# MCU.net
KiCad netlist of a schematic drawn in Altium Designer
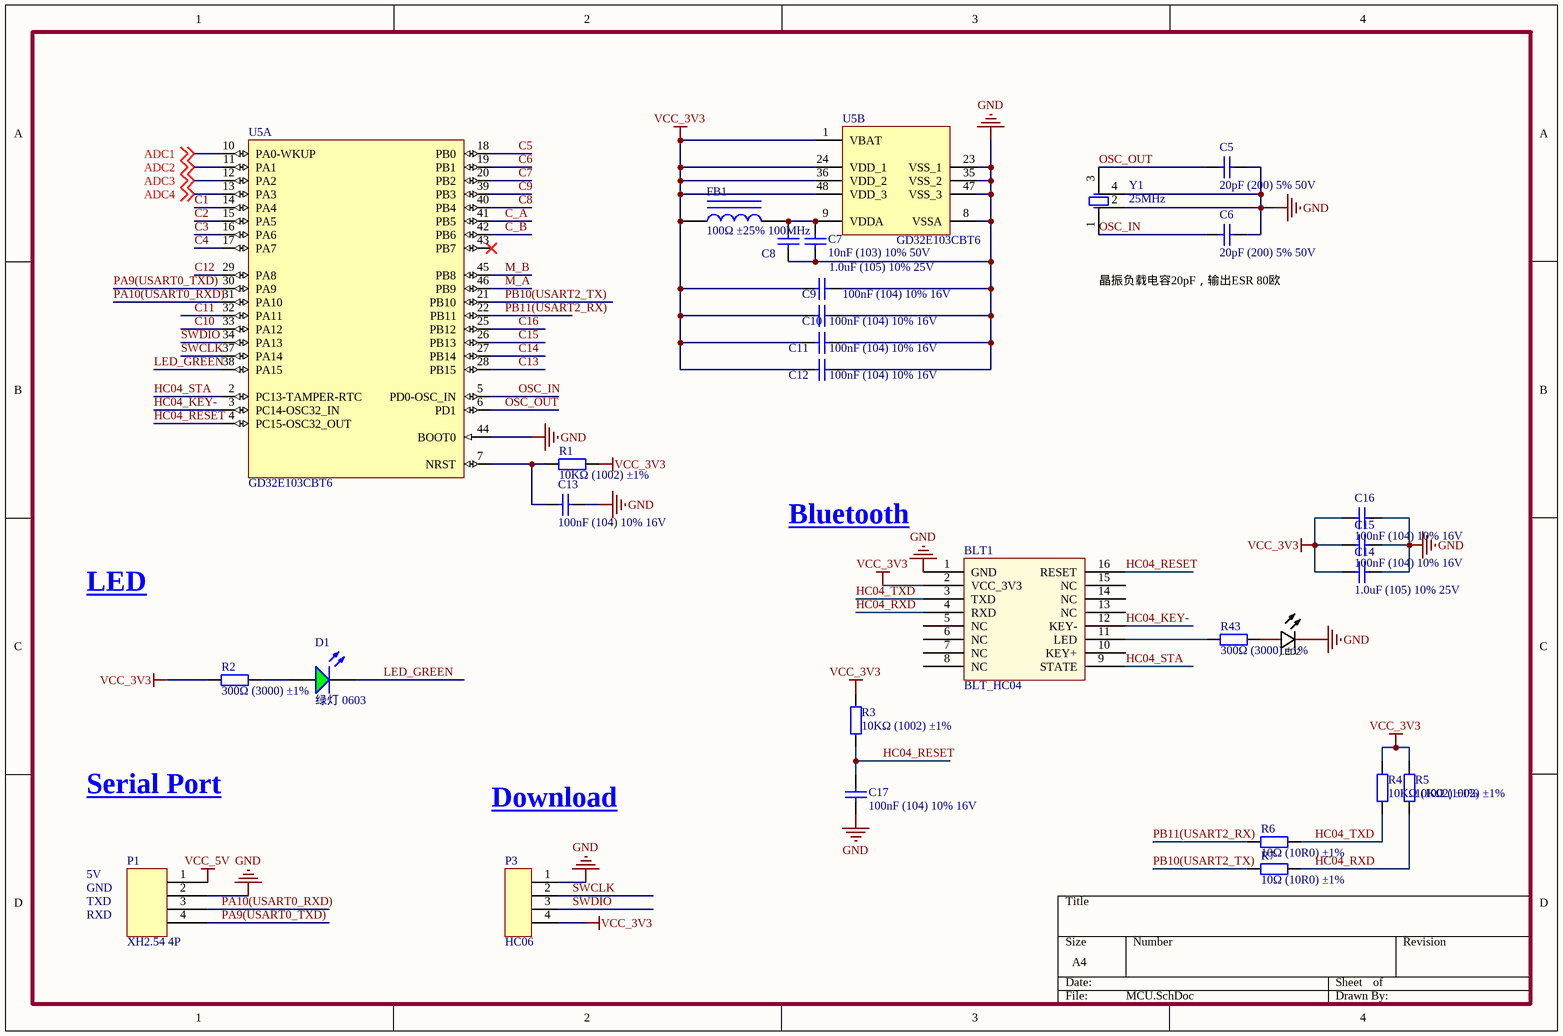
[diagram p0: MCU.SchDoc]

(export (version "E")
  (design (tool "Eeschema 10.0.6"))
  (components
    (comp (ref "BLT1")
      (value "BLT_HC04")
      (footprint "HC04_BLT")
      (libsource (lib "32x64_GD32E103VBT6") (part "BLT_HC04"))
    )
    (comp (ref "C5")
      (value "20pF (200) 5% 50V")
      (footprint "0402_C")
      (description "贴片电容")
      (libsource (lib "Miscellaneous Devices LC") (part "0402 20pF (200) 5% 50V"))
    )
    (comp (ref "C6")
      (value "20pF (200) 5% 50V")
      (footprint "0402_C")
      (description "贴片电容")
      (libsource (lib "Miscellaneous Devices LC") (part "0402 20pF (200) 5% 50V"))
    )
    (comp (ref "C7")
      (value "10nF (103) 10% 50V")
      (footprint "0402_C")
      (description "贴片电容")
      (libsource (lib "Miscellaneous Devices LC") (part "0402 10nF (103) 10% 50V"))
    )
    (comp (ref "C8")
      (value "1.0uF (105) 10% 25V")
      (footprint "0402_C")
      (description "贴片电容")
      (libsource (lib "EMOWHH Make") (part "0402-C"))
    )
    (comp (ref "C9")
      (value "100nF (104) 10% 16V")
      (footprint "0402_C")
      (description "贴片电容")
      (libsource (lib "EMOWHH Make") (part "0402-C"))
    )
    (comp (ref "C10")
      (value "100nF (104) 10% 16V")
      (footprint "0402_C")
      (description "贴片电容")
      (libsource (lib "EMOWHH Make") (part "0402-C"))
    )
    (comp (ref "C11")
      (value "100nF (104) 10% 16V")
      (footprint "0402_C")
      (description "贴片电容")
      (libsource (lib "EMOWHH Make") (part "0402-C"))
    )
    (comp (ref "C12")
      (value "100nF (104) 10% 16V")
      (footprint "0402_C")
      (description "贴片电容")
      (libsource (lib "EMOWHH Make") (part "0402-C"))
    )
    (comp (ref "C13")
      (value "100nF (104) 10% 16V")
      (footprint "0402_C")
      (description "贴片电容")
      (libsource (lib "Miscellaneous Devices LC") (part "0402 100nF (104) 10% 16V"))
    )
    (comp (ref "C14")
      (value "1.0uF (105) 10% 25V")
      (footprint "0402_C")
      (description "贴片电容")
      (libsource (lib "32x64_GD32E103VBT6") (part "0402 1.0uF (105) 10% 25V"))
    )
    (comp (ref "C15")
      (value "100nF (104) 10% 16V")
      (footprint "0402_C")
      (description "贴片电容")
      (libsource (lib "32x64_GD32E103VBT6") (part "0402 100nF (104) 10% 16V"))
    )
    (comp (ref "C16")
      (value "100nF (104) 10% 16V")
      (footprint "0402_C")
      (description "贴片电容")
      (libsource (lib "32x64_GD32E103VBT6") (part "0402 100nF (104) 10% 16V"))
    )
    (comp (ref "C17")
      (value "100nF (104) 10% 16V")
      (footprint "0402_C")
      (description "贴片电容")
      (libsource (lib "32x64_GD32E103VBT6") (part "0402 100nF (104) 10% 16V"))
    )
    (comp (ref "D1")
      (value "绿灯 0603")
      (footprint "0603_LED_S1")
      (description "发光二极管")
      (libsource (lib "Miscellaneous Devices LC") (part "0603 绿灯"))
    )
    (comp (ref "FB1")
      (value "100Ω ±25% 100MHz")
      (footprint "0805_L")
      (description "贴片磁珠")
      (libsource (lib "Miscellaneous Devices LC") (part "0805 100Ω 25% 100MHz"))
    )
    (comp (ref "LED2")
      (value "0603")
      (footprint "LED0603-RD")
      (description "0603 LED 蓝")
      (fields (field (name "MANUFACTURER") "国星光电") (field (name "MANUFACTURER PART") "NCD0603B4"))
      (libsource (lib "医疗床PCB") (part "0603 LED 蓝"))
    )
    (comp (ref "P1")
      (value "XH2.54 4P")
      (footprint "HC06")
      (libsource (lib "chaoning_Integrated_Library") (part "XH2.54 4P"))
    )
    (comp (ref "P3") (value "HC06") (footprint "HC06") (libsource (lib "EMOWHH Make") (part "HC06")))
    (comp (ref "R1")
      (value "10KΩ (1002) ±1%")
      (footprint "0402_R")
      (description "贴片电阻")
      (libsource (lib "Miscellaneous Devices LC") (part "0402 10KΩ (1002) 1%"))
    )
    (comp (ref "R2")
      (value "300Ω (3000) ±1%")
      (footprint "0402_R")
      (description "贴片电阻")
      (libsource (lib "") (part "0402 300Ω (3000) 1%_1"))
    )
    (comp (ref "R3")
      (value "10KΩ (1002) ±1%")
      (footprint "0402_R")
      (description "贴片电阻")
      (libsource (lib "32x64_GD32E103VBT6") (part "0402 10KΩ (1002) 1%"))
    )
    (comp (ref "R4")
      (value "10KΩ (1002) ±1%")
      (footprint "0402_R")
      (description "贴片电阻")
      (libsource (lib "32x64_GD32E103VBT6") (part "0402 10KΩ (1002) 1%"))
    )
    (comp (ref "R5")
      (value "10KΩ (1002) ±1%")
      (footprint "0402_R")
      (description "贴片电阻")
      (libsource (lib "32x64_GD32E103VBT6") (part "0402 10KΩ (1002) 1%"))
    )
    (comp (ref "R6")
      (value "10Ω (10R0) ±1%")
      (footprint "0402_R")
      (description "贴片电阻")
      (libsource (lib "32x64_GD32E103VBT6") (part "0402 10Ω (10R0) 1%"))
    )
    (comp (ref "R7")
      (value "10Ω (10R0) ±1%")
      (footprint "0402_R")
      (description "贴片电阻")
      (libsource (lib "32x64_GD32E103VBT6") (part "0402 10Ω (10R0) 1%"))
    )
    (comp (ref "R43")
      (value "300Ω (3000) ±1%")
      (footprint "0402_R")
      (description "贴片电阻")
      (libsource (lib "Miscellaneous Devices LC") (part "0402 300Ω (3000) 1%"))
    )
    (comp (ref "U5")
      (value "GD32E103CBT6")
      (footprint "LQFP48_N")
      (libsource (lib "dm-sch_library") (part "GD32E103CBT6"))
    )
    (comp (ref "Y1")
      (value "25MHz")
      (footprint "3225")
      (description "Crystal Oscillator")
      (fields (field (name "PUBLISHER") "Altium Limited"))
      (libsource (lib "chaoning_Integrated_Library") (part "XTAL-4"))
    )
  )
  (nets
    (net (code "2") (name "/C1") (class "Default")
      (node (ref "U5") (pin "14") (pinfunction "PA4_14") (pintype "bidirectional"))
    )
    (net (code "3") (name "/C2") (class "Default")
      (node (ref "U5") (pin "15") (pinfunction "PA5_15") (pintype "bidirectional"))
    )
    (net (code "4") (name "/C3") (class "Default")
      (node (ref "U5") (pin "16") (pinfunction "PA6_16") (pintype "bidirectional"))
    )
    (net (code "5") (name "/C4") (class "Default")
      (node (ref "U5") (pin "17") (pinfunction "PA7_17") (pintype "bidirectional"))
    )
    (net (code "6") (name "/C5") (class "Default")
      (node (ref "U5") (pin "18") (pinfunction "PB0_18") (pintype "bidirectional"))
    )
    (net (code "7") (name "/C6") (class "Default")
      (node (ref "U5") (pin "19") (pinfunction "PB1_19") (pintype "bidirectional"))
    )
    (net (code "8") (name "/C7") (class "Default")
      (node (ref "U5") (pin "20") (pinfunction "PB2_20") (pintype "bidirectional"))
    )
    (net (code "9") (name "/C8") (class "Default")
      (node (ref "U5") (pin "40") (pinfunction "PB4_40") (pintype "bidirectional"))
    )
    (net (code "10") (name "/C9") (class "Default")
      (node (ref "U5") (pin "39") (pinfunction "PB3_39") (pintype "bidirectional"))
    )
    (net (code "11") (name "/C10") (class "Default")
      (node (ref "U5") (pin "33") (pinfunction "PA12_33") (pintype "bidirectional"))
    )
    (net (code "12") (name "/C11") (class "Default")
      (node (ref "U5") (pin "32") (pinfunction "PA11_32") (pintype "bidirectional"))
    )
    (net (code "13") (name "/C12") (class "Default")
      (node (ref "U5") (pin "29") (pinfunction "PA8_29") (pintype "bidirectional"))
    )
    (net (code "14") (name "/C13") (class "Default")
      (node (ref "U5") (pin "28") (pinfunction "PB15_28") (pintype "bidirectional"))
    )
    (net (code "15") (name "/C14") (class "Default")
      (node (ref "U5") (pin "27") (pinfunction "PB14_27") (pintype "bidirectional"))
    )
    (net (code "16") (name "/C15") (class "Default")
      (node (ref "U5") (pin "26") (pinfunction "PB13_26") (pintype "bidirectional"))
    )
    (net (code "17") (name "/C16") (class "Default")
      (node (ref "U5") (pin "25") (pinfunction "PB12_25") (pintype "bidirectional"))
    )
    (net (code "18") (name "/C_A") (class "Default")
      (node (ref "U5") (pin "41") (pinfunction "PB5_41") (pintype "bidirectional"))
    )
    (net (code "19") (name "/C_B") (class "Default")
      (node (ref "U5") (pin "42") (pinfunction "PB6_42") (pintype "bidirectional"))
    )
    (net (code "20") (name "/HC04_KEY-") (class "Default")
      (node (ref "BLT1") (pin "12") (pinfunction "KEY-_12") (pintype "passive"))
      (node (ref "U5") (pin "3") (pinfunction "PC14-OSC32_IN_3") (pintype "bidirectional"))
    )
    (net (code "21") (name "/HC04_RESET") (class "Default")
      (node (ref "BLT1") (pin "16") (pinfunction "RESET_16") (pintype "passive"))
      (node (ref "C17") (pin "2") (pinfunction "2_2") (pintype "passive"))
      (node (ref "R3") (pin "1") (pinfunction "1_1") (pintype "passive"))
      (node (ref "U5") (pin "4") (pinfunction "PC15-OSC32_OUT_4") (pintype "bidirectional"))
    )
    (net (code "22") (name "/HC04_RXD") (class "Default")
      (node (ref "BLT1") (pin "4") (pinfunction "RXD_4") (pintype "passive"))
      (node (ref "R5") (pin "1") (pinfunction "1_1") (pintype "passive"))
      (node (ref "R7") (pin "2") (pinfunction "2_2") (pintype "passive"))
    )
    (net (code "23") (name "/HC04_STA") (class "Default")
      (node (ref "BLT1") (pin "9") (pinfunction "STATE_9") (pintype "passive"))
      (node (ref "U5") (pin "2") (pinfunction "PC13-TAMPER-RTC_2") (pintype "bidirectional"))
    )
    (net (code "24") (name "/HC04_TXD") (class "Default")
      (node (ref "BLT1") (pin "3") (pinfunction "TXD_3") (pintype "passive"))
      (node (ref "R4") (pin "1") (pinfunction "1_1") (pintype "passive"))
      (node (ref "R6") (pin "2") (pinfunction "2_2") (pintype "passive"))
    )
    (net (code "25") (name "/LED_GREEN") (class "Default")
      (node (ref "D1") (pin "K") (pinfunction "K_K") (pintype "passive"))
      (node (ref "U5") (pin "38") (pinfunction "PA15_38") (pintype "bidirectional"))
    )
    (net (code "26") (name "/M_A") (class "Default")
      (node (ref "U5") (pin "46") (pinfunction "PB9_46") (pintype "bidirectional"))
    )
    (net (code "27") (name "/M_B") (class "Default")
      (node (ref "U5") (pin "45") (pinfunction "PB8_45") (pintype "bidirectional"))
    )
    (net (code "28") (name "/OSC_IN") (class "Default")
      (node (ref "C6") (pin "1") (pinfunction "1_1") (pintype "passive"))
      (node (ref "U5") (pin "5") (pinfunction "PD0-OSC_IN_5") (pintype "bidirectional"))
      (node (ref "Y1") (pin "1") (pinfunction "OSC2_1") (pintype "passive"))
    )
    (net (code "29") (name "/OSC_OUT") (class "Default")
      (node (ref "C5") (pin "1") (pinfunction "1_1") (pintype "passive"))
      (node (ref "U5") (pin "6") (pinfunction "PD1_6") (pintype "bidirectional"))
      (node (ref "Y1") (pin "3") (pinfunction "OSC1_3") (pintype "passive"))
    )
    (net (code "30") (name "/PA9(USART0_TXD)") (class "Default")
      (node (ref "P1") (pin "4") (pinfunction "4_4") (pintype "passive"))
      (node (ref "U5") (pin "30") (pinfunction "PA9_30") (pintype "bidirectional"))
    )
    (net (code "31") (name "/PA10(USART0_RXD)") (class "Default")
      (node (ref "P1") (pin "3") (pinfunction "3_3") (pintype "passive"))
      (node (ref "U5") (pin "31") (pinfunction "PA10_31") (pintype "bidirectional"))
    )
    (net (code "32") (name "/PB10(USART2_TX)") (class "Default")
      (node (ref "R7") (pin "1") (pinfunction "1_1") (pintype "passive"))
      (node (ref "U5") (pin "21") (pinfunction "PB10_21") (pintype "bidirectional"))
    )
    (net (code "33") (name "/PB11(USART2_RX)") (class "Default")
      (node (ref "R6") (pin "1") (pinfunction "1_1") (pintype "passive"))
      (node (ref "U5") (pin "22") (pinfunction "PB11_22") (pintype "bidirectional"))
    )
    (net (code "34") (name "/SWCLK") (class "Default")
      (node (ref "P3") (pin "2") (pinfunction "2_2") (pintype "passive"))
      (node (ref "U5") (pin "37") (pinfunction "PA14_37") (pintype "bidirectional"))
    )
    (net (code "35") (name "/SWDIO") (class "Default")
      (node (ref "P3") (pin "3") (pinfunction "3_3") (pintype "passive"))
      (node (ref "U5") (pin "34") (pinfunction "PA13_34") (pintype "bidirectional"))
    )
    (net (code "36") (name "ADC1") (class "Default")
      (node (ref "U5") (pin "10") (pinfunction "PA0-WKUP_10") (pintype "bidirectional"))
    )
    (net (code "37") (name "ADC2") (class "Default")
      (node (ref "U5") (pin "11") (pinfunction "PA1_11") (pintype "bidirectional"))
    )
    (net (code "38") (name "ADC3") (class "Default")
      (node (ref "U5") (pin "12") (pinfunction "PA2_12") (pintype "bidirectional"))
    )
    (net (code "39") (name "ADC4") (class "Default")
      (node (ref "U5") (pin "13") (pinfunction "PA3_13") (pintype "bidirectional"))
    )
    (net (code "40") (name "GND") (class "Default")
      (node (ref "BLT1") (pin "1") (pinfunction "GND_1") (pintype "passive"))
      (node (ref "C10") (pin "2") (pinfunction "2_2") (pintype "passive"))
      (node (ref "C11") (pin "2") (pinfunction "2_2") (pintype "passive"))
      (node (ref "C12") (pin "2") (pinfunction "2_2") (pintype "passive"))
      (node (ref "C13") (pin "2") (pinfunction "2_2") (pintype "passive"))
      (node (ref "C14") (pin "1") (pinfunction "1_1") (pintype "passive"))
      (node (ref "C15") (pin "1") (pinfunction "1_1") (pintype "passive"))
      (node (ref "C16") (pin "1") (pinfunction "1_1") (pintype "passive"))
      (node (ref "C17") (pin "1") (pinfunction "1_1") (pintype "passive"))
      (node (ref "C5") (pin "2") (pinfunction "2_2") (pintype "passive"))
      (node (ref "C6") (pin "2") (pinfunction "2_2") (pintype "passive"))
      (node (ref "C7") (pin "1") (pinfunction "1_1") (pintype "passive"))
      (node (ref "C8") (pin "2") (pinfunction "2_2") (pintype "passive"))
      (node (ref "C9") (pin "2") (pinfunction "2_2") (pintype "passive"))
      (node (ref "LED2") (pin "2") (pinfunction "K_2") (pintype "passive"))
      (node (ref "P1") (pin "2") (pinfunction "2_2") (pintype "passive"))
      (node (ref "P3") (pin "1") (pinfunction "1_1") (pintype "passive"))
      (node (ref "U5") (pin "23") (pinfunction "VSS_1_23") (pintype "power_in"))
      (node (ref "U5") (pin "35") (pinfunction "VSS_2_35") (pintype "power_in"))
      (node (ref "U5") (pin "44") (pinfunction "BOOT0_44") (pintype "input"))
      (node (ref "U5") (pin "47") (pinfunction "VSS_3_47") (pintype "power_in"))
      (node (ref "U5") (pin "8") (pinfunction "VSSA_8") (pintype "power_in"))
      (node (ref "Y1") (pin "2") (pinfunction "HIN4_2") (pintype "passive"))
      (node (ref "Y1") (pin "4") (pinfunction "HIN4_4") (pintype "passive"))
    )
    (net (code "41") (name "Net-(BLT1-LED)") (class "Default")
      (node (ref "BLT1") (pin "11") (pinfunction "LED_11") (pintype "passive"))
      (node (ref "R43") (pin "2") (pinfunction "2_2") (pintype "passive"))
    )
    (net (code "42") (name "Net-(D1-PadA)") (class "Default")
      (node (ref "D1") (pin "A") (pinfunction "A_A") (pintype "passive"))
      (node (ref "R2") (pin "2") (pinfunction "2_2") (pintype "passive"))
    )
    (net (code "43") (name "Net-(LED2-A)") (class "Default")
      (node (ref "LED2") (pin "1") (pinfunction "A_1") (pintype "passive"))
      (node (ref "R43") (pin "1") (pinfunction "1_1") (pintype "passive"))
    )
    (net (code "44") (name "Net-(U5A-NRST)") (class "Default")
      (node (ref "C13") (pin "1") (pinfunction "1_1") (pintype "passive"))
      (node (ref "R1") (pin "1") (pinfunction "1_1") (pintype "passive"))
      (node (ref "U5") (pin "7") (pinfunction "NRST_7") (pintype "bidirectional"))
    )
    (net (code "45") (name "Net-(U5B-VDDA)") (class "Default")
      (node (ref "C7") (pin "2") (pinfunction "2_2") (pintype "passive"))
      (node (ref "C8") (pin "1") (pinfunction "1_1") (pintype "passive"))
      (node (ref "FB1") (pin "2") (pinfunction "2_2") (pintype "passive"))
      (node (ref "U5") (pin "9") (pinfunction "VDDA_9") (pintype "power_in"))
    )
    (net (code "46") (name "VCC_3V3") (class "Default")
      (node (ref "BLT1") (pin "2") (pinfunction "VCC_3V3_2") (pintype "passive"))
      (node (ref "C10") (pin "1") (pinfunction "1_1") (pintype "passive"))
      (node (ref "C11") (pin "1") (pinfunction "1_1") (pintype "passive"))
      (node (ref "C12") (pin "1") (pinfunction "1_1") (pintype "passive"))
      (node (ref "C14") (pin "2") (pinfunction "2_2") (pintype "passive"))
      (node (ref "C15") (pin "2") (pinfunction "2_2") (pintype "passive"))
      (node (ref "C16") (pin "2") (pinfunction "2_2") (pintype "passive"))
      (node (ref "C9") (pin "1") (pinfunction "1_1") (pintype "passive"))
      (node (ref "FB1") (pin "1") (pinfunction "1_1") (pintype "passive"))
      (node (ref "P3") (pin "4") (pinfunction "4_4") (pintype "passive"))
      (node (ref "R1") (pin "2") (pinfunction "2_2") (pintype "passive"))
      (node (ref "R2") (pin "1") (pinfunction "1_1") (pintype "passive"))
      (node (ref "R3") (pin "2") (pinfunction "2_2") (pintype "passive"))
      (node (ref "R4") (pin "2") (pinfunction "2_2") (pintype "passive"))
      (node (ref "R5") (pin "2") (pinfunction "2_2") (pintype "passive"))
      (node (ref "U5") (pin "1") (pinfunction "VBAT_1") (pintype "power_in"))
      (node (ref "U5") (pin "24") (pinfunction "VDD_1_24") (pintype "power_in"))
      (node (ref "U5") (pin "36") (pinfunction "VDD_2_36") (pintype "power_in"))
      (node (ref "U5") (pin "48") (pinfunction "VDD_3_48") (pintype "power_in"))
    )
    (net (code "47") (name "VCC_5V") (class "Default")
      (node (ref "P1") (pin "1") (pinfunction "1_1") (pintype "passive"))
    )
    (net (code "48") (name "unconnected-(BLT1-KEY+-Pad10)") (class "Default")
      (node (ref "BLT1") (pin "10") (pinfunction "KEY+_10") (pintype "passive"))
    )
    (net (code "49") (name "unconnected-(BLT1-NC-Pad5)") (class "Default")
      (node (ref "BLT1") (pin "5") (pinfunction "NC_5") (pintype "passive"))
    )
    (net (code "50") (name "unconnected-(BLT1-NC-Pad6)") (class "Default")
      (node (ref "BLT1") (pin "6") (pinfunction "NC_6") (pintype "passive"))
    )
    (net (code "51") (name "unconnected-(BLT1-NC-Pad7)") (class "Default")
      (node (ref "BLT1") (pin "7") (pinfunction "NC_7") (pintype "passive"))
    )
    (net (code "52") (name "unconnected-(BLT1-NC-Pad8)") (class "Default")
      (node (ref "BLT1") (pin "8") (pinfunction "NC_8") (pintype "passive"))
    )
    (net (code "53") (name "unconnected-(BLT1-NC-Pad13)") (class "Default")
      (node (ref "BLT1") (pin "13") (pinfunction "NC_13") (pintype "passive"))
    )
    (net (code "54") (name "unconnected-(BLT1-NC-Pad14)") (class "Default")
      (node (ref "BLT1") (pin "14") (pinfunction "NC_14") (pintype "passive"))
    )
    (net (code "55") (name "unconnected-(BLT1-NC-Pad15)") (class "Default")
      (node (ref "BLT1") (pin "15") (pinfunction "NC_15") (pintype "passive"))
    )
    (net (code "56") (name "unconnected-(U5A-PB7-Pad43)") (class "Default")
      (node (ref "U5") (pin "43") (pinfunction "PB7_43") (pintype "bidirectional+no_connect"))
    )
  )
)
